# AC_DIMMER.net
KiCad netlist of a schematic drawn in EAGLE
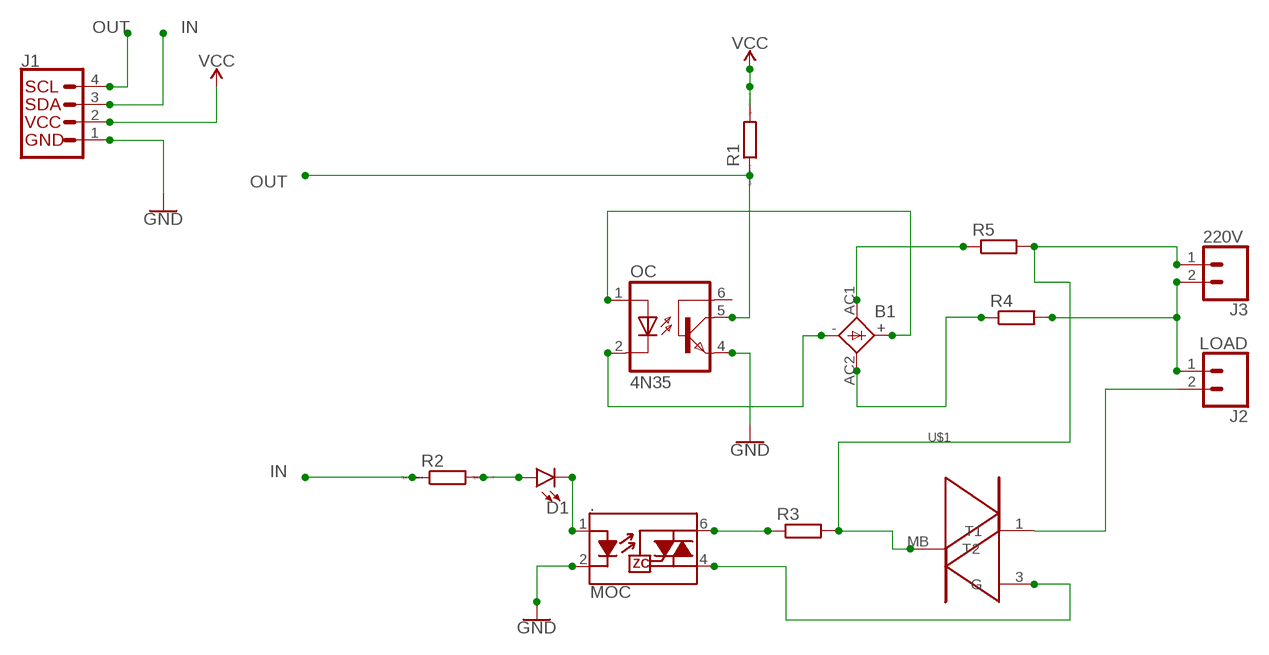
[diagram p0: schematic, sheet 1]

(export (version "E")
  (design (tool "Eeschema 10.0.6"))
  (components
    (comp (ref ".")
      (value "MOC")
      (footprint "eagle-import:DIP8SMD")
      (libsource (lib "eagle-import") (part "TRIAC_OPTOCOUPLER-MOC3063SM"))
    )
    (comp (ref "B1")
      (value "2KBP")
      (footprint "eagle-import:2KBP")
      (libsource (lib "eagle-import") (part "2KBP"))
    )
    (comp (ref "D1")
      (value "LED-FKIT-1206")
      (footprint "eagle-import:FKIT-LED-1206")
      (libsource (lib "eagle-import") (part "LED-FKIT-1206"))
    )
    (comp (ref "J1")
      (value "QWIIC_CONNECTORJS-1MM")
      (footprint "eagle-import:1X04_1MM_RA")
      (libsource (lib "eagle-import") (part "QWIIC_CONNECTORJS-1MM"))
    )
    (comp (ref "J2")
      (value "LOAD")
      (footprint "eagle-import:SCREWTERMINAL-3.5MM-2")
      (libsource (lib "eagle-import") (part "CONN_023.5MM"))
    )
    (comp (ref "J3")
      (value "220V")
      (footprint "eagle-import:SCREWTERMINAL-3.5MM-2")
      (libsource (lib "eagle-import") (part "CONN_023.5MM"))
    )
    (comp (ref "OC")
      (value "4N35")
      (footprint "eagle-import:DIL6-SMD")
      (fields (field (name "MF") "FAIRCHILD SEMICONDUCTOR") (field (name "MPN") "4N35S-M"))
      (libsource (lib "eagle-import") (part "4N?MS35"))
    )
    (comp (ref "R1")
      (value "RR0603")
      (footprint "eagle-import:R0603")
      (libsource (lib "eagle-import") (part "RR0603"))
    )
    (comp (ref "R2")
      (value "RR0603")
      (footprint "eagle-import:R0603")
      (libsource (lib "eagle-import") (part "RR0603"))
    )
    (comp (ref "R3")
      (value "R-EU_R3225")
      (footprint "eagle-import:R3225")
      (libsource (lib "eagle-import") (part "R-EU_R3225"))
    )
    (comp (ref "R4")
      (value "R-EU_R3225")
      (footprint "eagle-import:R3225")
      (libsource (lib "eagle-import") (part "R-EU_R3225"))
    )
    (comp (ref "R5")
      (value "R-EU_R3225")
      (footprint "eagle-import:R3225")
      (libsource (lib "eagle-import") (part "R-EU_R3225"))
    )
    (comp (ref "U$1")
      (value "BT136S-600ETRIACA")
      (footprint "eagle-import:SOT428")
      (libsource (lib "eagle-import") (part "BT136S-600EATRIAC"))
    )
  )
  (nets
    (net (code "1") (name "/IN") (class "Default")
      (node (ref "J1") (pin "3") (pinfunction "SDA_3") (pintype "passive"))
      (node (ref "R2") (pin "1") (pinfunction "1_1") (pintype "passive"))
    )
    (net (code "2") (name "/OUT") (class "Default")
      (node (ref "J1") (pin "4") (pinfunction "SCL_4") (pintype "passive"))
      (node (ref "OC") (pin "5") (pinfunction "COL_5") (pintype "passive"))
      (node (ref "R1") (pin "1") (pinfunction "1_1") (pintype "passive"))
    )
    (net (code "3") (name "GND") (class "Default")
      (node (ref ".") (pin "2") (pinfunction "K_2") (pintype "bidirectional"))
      (node (ref "J1") (pin "1") (pinfunction "GND_1") (pintype "power_in"))
      (node (ref "OC") (pin "4") (pinfunction "EMI_4") (pintype "passive"))
    )
    (net (code "4") (name "Net-(.-A)") (class "Default")
      (node (ref ".") (pin "1") (pinfunction "A_1") (pintype "bidirectional"))
      (node (ref "D1") (pin "C") (pinfunction "C_C") (pintype "passive"))
    )
    (net (code "5") (name "Net-(.-T1)") (class "Default")
      (node (ref ".") (pin "6") (pinfunction "T1_6") (pintype "bidirectional"))
      (node (ref "R3") (pin "1") (pinfunction "1_1") (pintype "passive"))
    )
    (net (code "6") (name "Net-(.-T2)") (class "Default")
      (node (ref ".") (pin "4") (pinfunction "T2_4") (pintype "bidirectional"))
      (node (ref "U$1") (pin "3") (pinfunction "G_3") (pintype "bidirectional"))
    )
    (net (code "7") (name "Net-(B1-PadAC1)") (class "Default")
      (node (ref "B1") (pin "AC1") (pinfunction "AC1_AC1") (pintype "passive"))
      (node (ref "R5") (pin "1") (pinfunction "1_1") (pintype "passive"))
    )
    (net (code "8") (name "Net-(B1-PadAC2)") (class "Default")
      (node (ref "B1") (pin "AC2") (pinfunction "AC2_AC2") (pintype "passive"))
      (node (ref "R4") (pin "1") (pinfunction "1_1") (pintype "passive"))
    )
    (net (code "9") (name "Net-(D1-PadA)") (class "Default")
      (node (ref "D1") (pin "A") (pinfunction "A_A") (pintype "passive"))
      (node (ref "R2") (pin "2") (pinfunction "2_2") (pintype "passive"))
    )
    (net (code "10") (name "Net-(J2-Pad1)") (class "Default")
      (node (ref "J2") (pin "1") (pinfunction "1_1") (pintype "passive"))
      (node (ref "J3") (pin "2") (pinfunction "2_2") (pintype "passive"))
      (node (ref "R4") (pin "2") (pinfunction "2_2") (pintype "passive"))
    )
    (net (code "11") (name "Net-(OC-A)") (class "Default")
      (node (ref "B1") (pin "+") (pinfunction "+_+") (pintype "passive"))
      (node (ref "OC") (pin "1") (pinfunction "A_1") (pintype "passive"))
    )
    (net (code "12") (name "Net-(OC-C)") (class "Default")
      (node (ref "B1") (pin "-") (pinfunction "-_-") (pintype "passive"))
      (node (ref "OC") (pin "2") (pinfunction "C_2") (pintype "passive"))
    )
    (net (code "13") (name "Net-(U$1-T1)") (class "Default")
      (node (ref "J2") (pin "2") (pinfunction "2_2") (pintype "passive"))
      (node (ref "U$1") (pin "1") (pinfunction "T1_1") (pintype "bidirectional"))
    )
    (net (code "14") (name "Net-(U$1-T2)") (class "Default")
      (node (ref "J3") (pin "1") (pinfunction "1_1") (pintype "passive"))
      (node (ref "R3") (pin "2") (pinfunction "2_2") (pintype "passive"))
      (node (ref "R5") (pin "2") (pinfunction "2_2") (pintype "passive"))
      (node (ref "U$1") (pin "MB") (pinfunction "T2_MB") (pintype "bidirectional"))
    )
    (net (code "15") (name "VCC") (class "Default")
      (node (ref "J1") (pin "2") (pinfunction "VCC_2") (pintype "power_in"))
      (node (ref "R1") (pin "2") (pinfunction "2_2") (pintype "passive"))
    )
    (net (code "16") (name "unconnected-(OC-BAS-Pad6)") (class "Default")
      (node (ref "OC") (pin "6") (pinfunction "BAS_6") (pintype "passive"))
    )
  )
)
